# Charger_Board.net
KiCad netlist of a schematic drawn in EAGLE
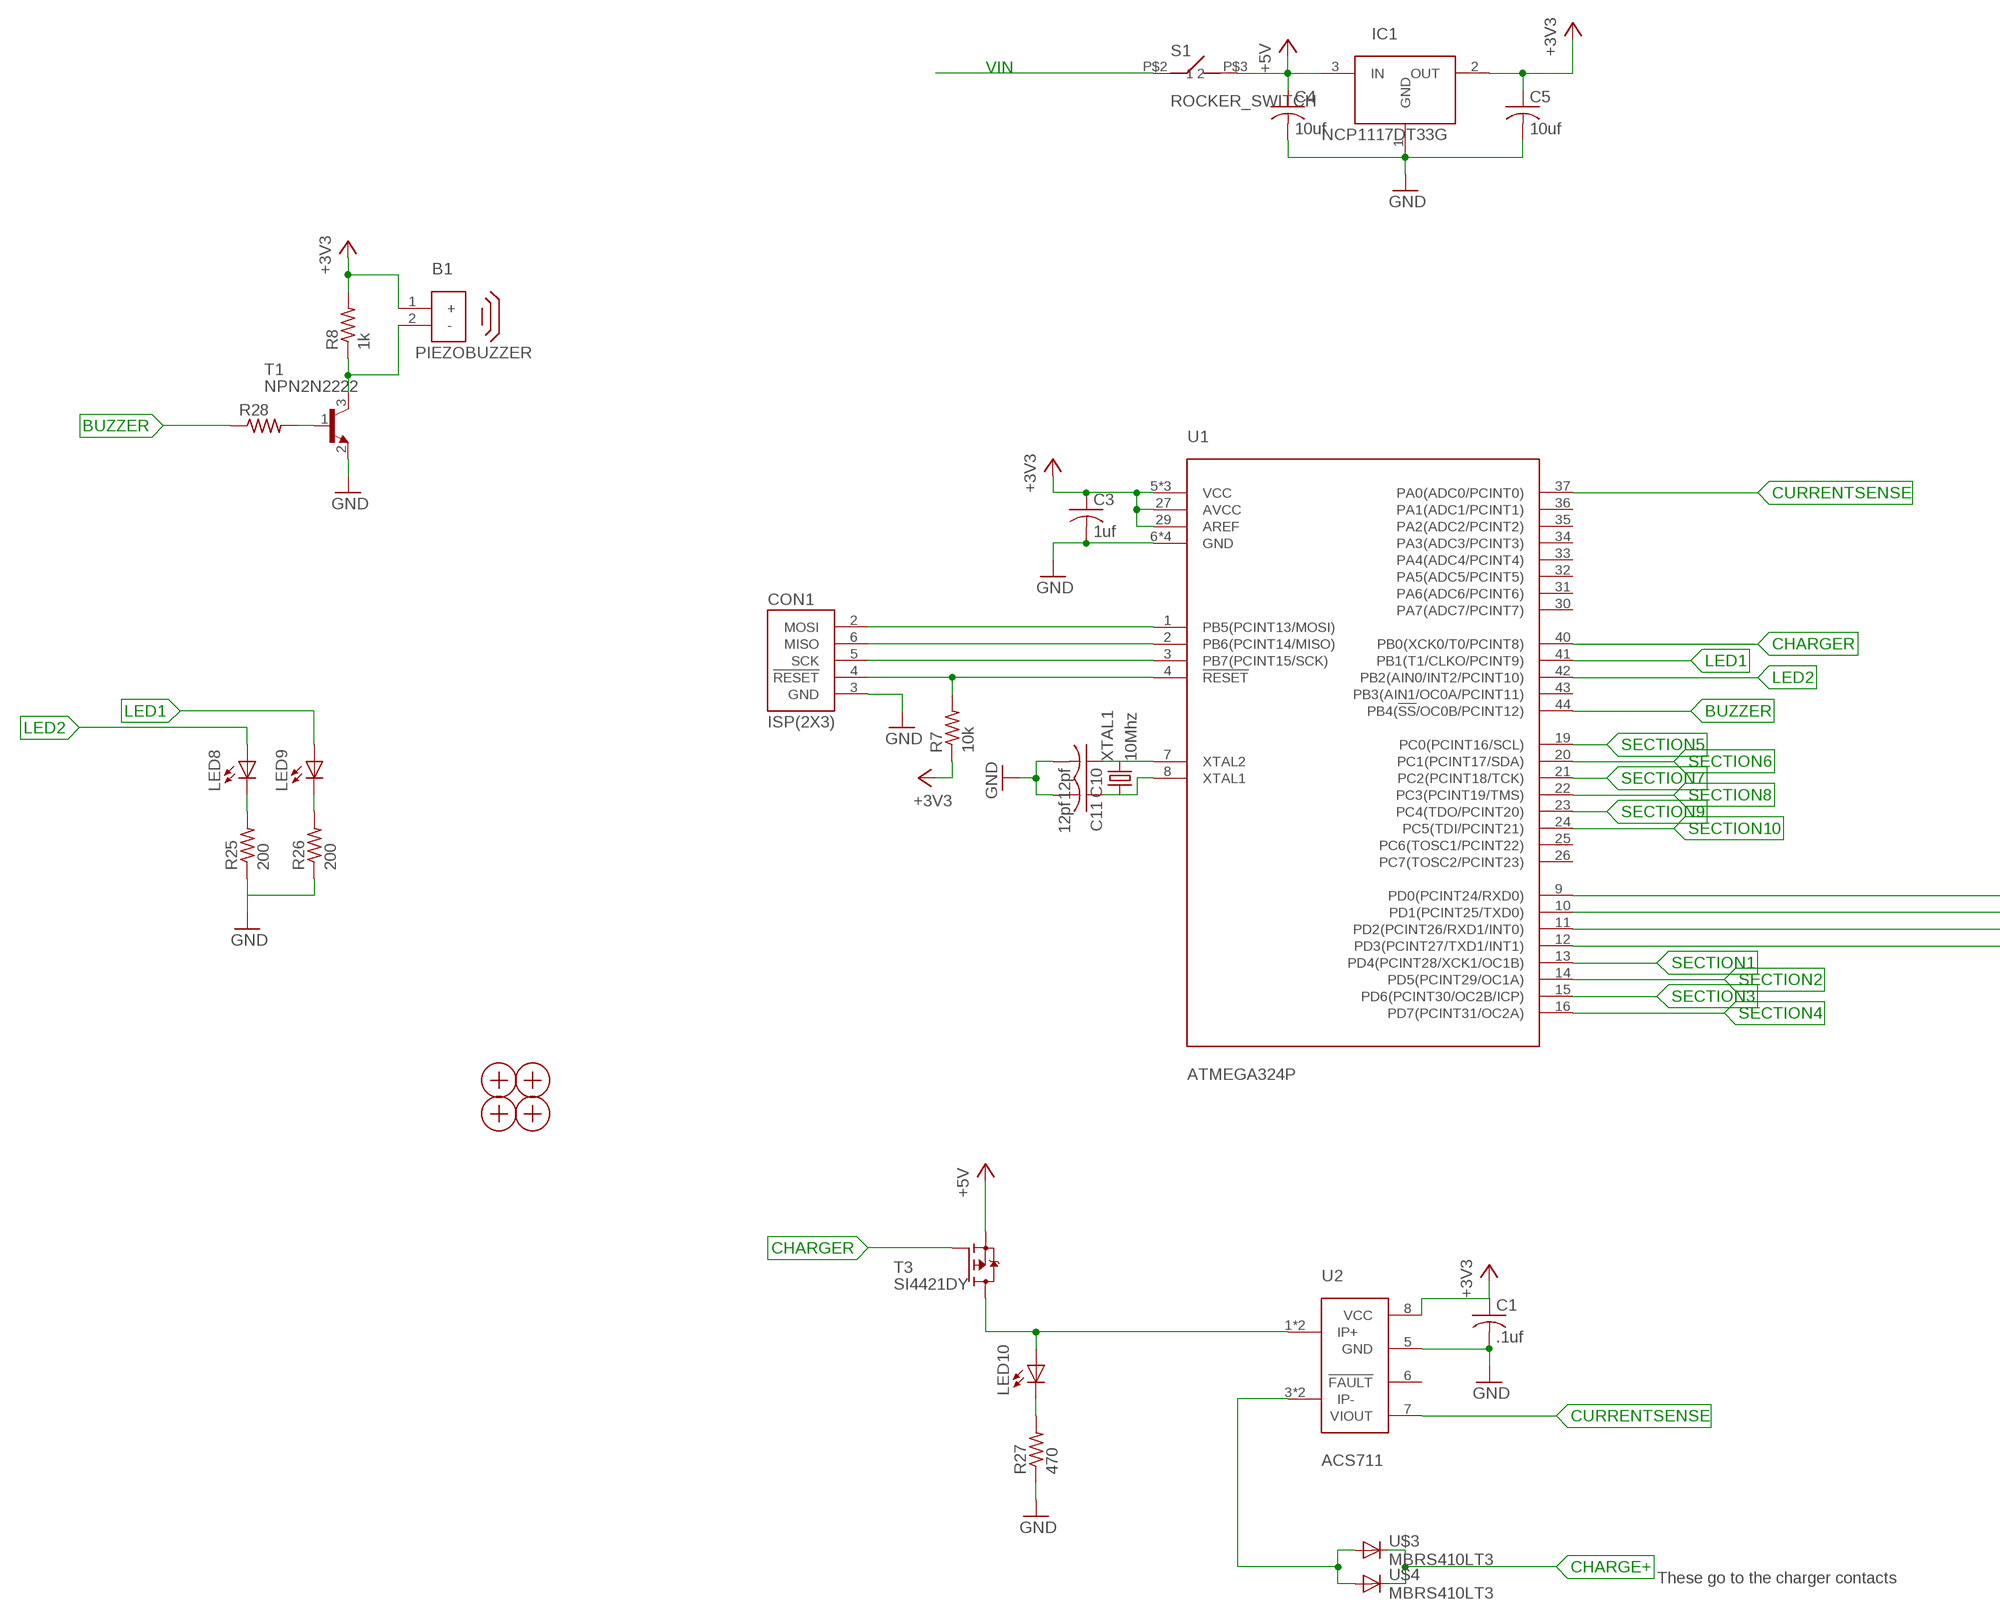
[diagram p0: schematic, sheet 1, part 1 of 2]
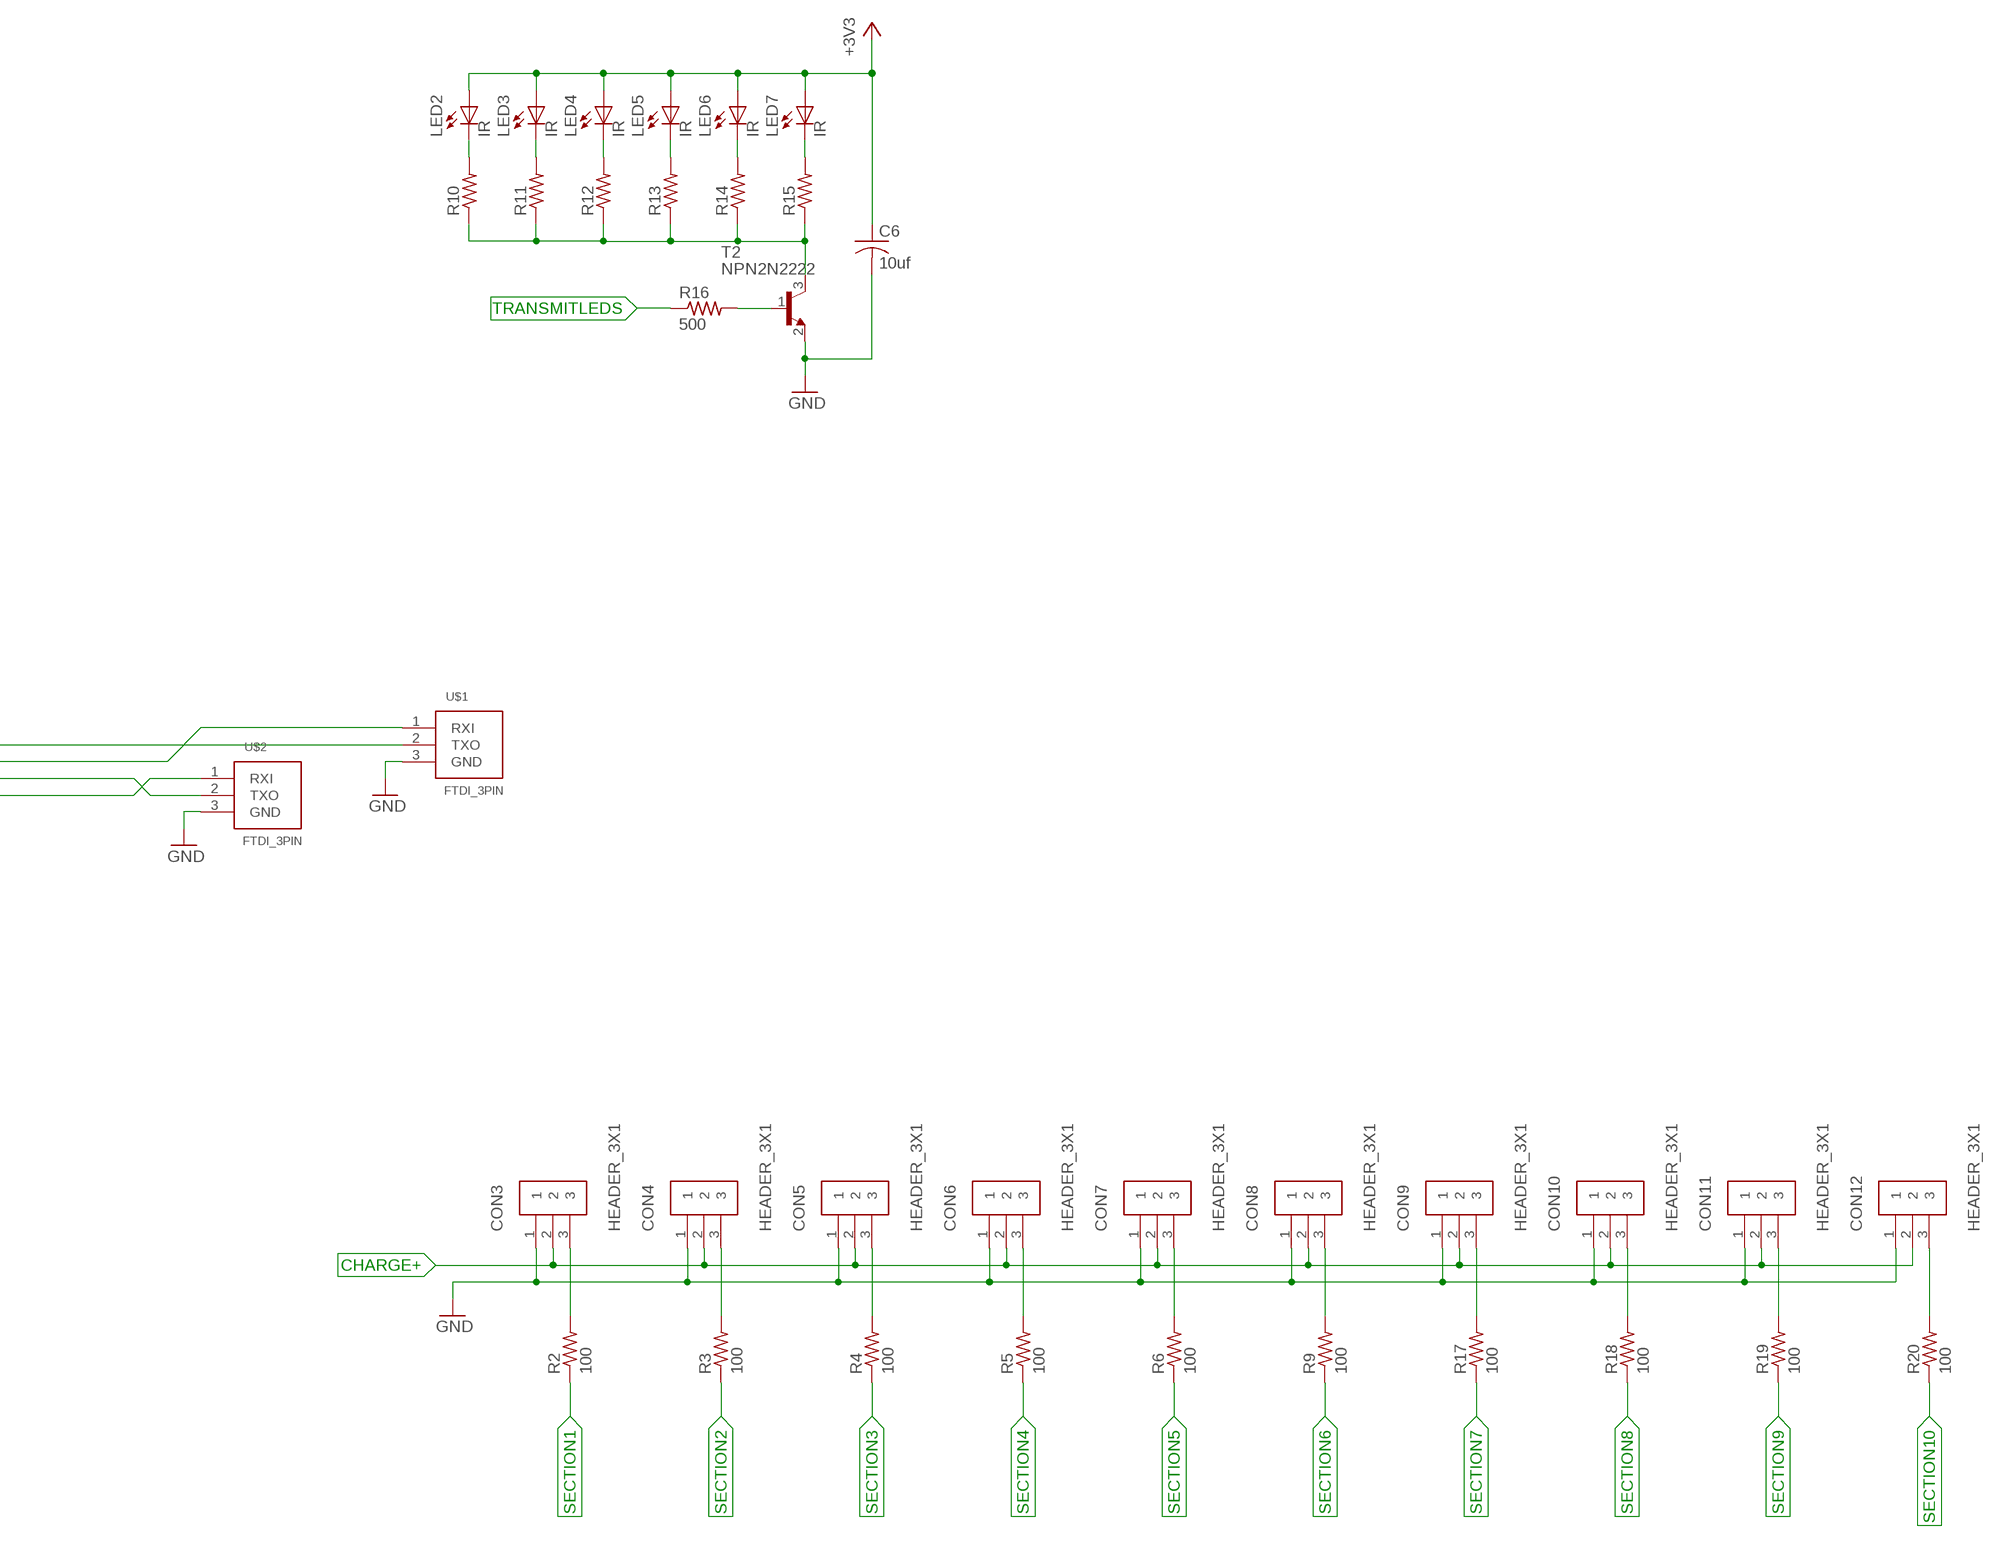
[diagram p1: schematic, sheet 1, part 2 of 2]

(export (version "E")
  (design (tool "Eeschema 10.0.6"))
  (components
    (comp (ref "B1")
      (value "PIEZOBUZZER")
      (footprint "eagle-import:PIEZOBUZZER")
      (libsource (lib "eagle-import") (part "PIEZOBUZZER"))
    )
    (comp (ref "C1")
      (value ".1uf")
      (footprint "eagle-import:0603")
      (libsource (lib "eagle-import") (part "CAP0603"))
    )
    (comp (ref "C3")
      (value "1uf")
      (footprint "eagle-import:0603")
      (libsource (lib "eagle-import") (part "CAP0603"))
    )
    (comp (ref "C4")
      (value "10uf")
      (footprint "eagle-import:0805")
      (libsource (lib "eagle-import") (part "CAP0805"))
    )
    (comp (ref "C5")
      (value "10uf")
      (footprint "eagle-import:0805")
      (libsource (lib "eagle-import") (part "CAP0805"))
    )
    (comp (ref "C6")
      (value "10uf")
      (footprint "eagle-import:0805")
      (libsource (lib "eagle-import") (part "CAP0805"))
    )
    (comp (ref "C10")
      (value "12pf")
      (footprint "eagle-import:0603")
      (libsource (lib "eagle-import") (part "CAP0603"))
    )
    (comp (ref "C11")
      (value "12pf")
      (footprint "eagle-import:0603")
      (libsource (lib "eagle-import") (part "CAP0603"))
    )
    (comp (ref "CON1")
      (value "ISP(2X3)")
      (footprint "eagle-import:PINHEADER(2X3)")
      (libsource (lib "eagle-import") (part "ISP(2X3)"))
    )
    (comp (ref "CON3")
      (value "HEADER_3X1")
      (footprint "eagle-import:3PINHEADER_.100_")
      (libsource (lib "eagle-import") (part "HEADER_3X1"))
    )
    (comp (ref "CON4")
      (value "HEADER_3X1")
      (footprint "eagle-import:3PINHEADER_.100_")
      (libsource (lib "eagle-import") (part "HEADER_3X1"))
    )
    (comp (ref "CON5")
      (value "HEADER_3X1")
      (footprint "eagle-import:3PINHEADER_.100_")
      (libsource (lib "eagle-import") (part "HEADER_3X1"))
    )
    (comp (ref "CON6")
      (value "HEADER_3X1")
      (footprint "eagle-import:3PINHEADER_.100_")
      (libsource (lib "eagle-import") (part "HEADER_3X1"))
    )
    (comp (ref "CON7")
      (value "HEADER_3X1")
      (footprint "eagle-import:3PINHEADER_.100_")
      (libsource (lib "eagle-import") (part "HEADER_3X1"))
    )
    (comp (ref "CON8")
      (value "HEADER_3X1")
      (footprint "eagle-import:3PINHEADER_.100_")
      (libsource (lib "eagle-import") (part "HEADER_3X1"))
    )
    (comp (ref "CON9")
      (value "HEADER_3X1")
      (footprint "eagle-import:3PINHEADER_.100_")
      (libsource (lib "eagle-import") (part "HEADER_3X1"))
    )
    (comp (ref "CON10")
      (value "HEADER_3X1")
      (footprint "eagle-import:3PINHEADER_.100_")
      (libsource (lib "eagle-import") (part "HEADER_3X1"))
    )
    (comp (ref "CON11")
      (value "HEADER_3X1")
      (footprint "eagle-import:3PINHEADER_.100_")
      (libsource (lib "eagle-import") (part "HEADER_3X1"))
    )
    (comp (ref "CON12")
      (value "HEADER_3X1")
      (footprint "eagle-import:3PINHEADER_.100_")
      (libsource (lib "eagle-import") (part "HEADER_3X1"))
    )
    (comp (ref "H1")
      (value "MOUNTINGHOLE")
      (footprint "eagle-import:MOUNTINGHOLE")
      (libsource (lib "eagle-import") (part "MOUNTINGHOLE"))
    )
    (comp (ref "H2")
      (value "MOUNTINGHOLE")
      (footprint "eagle-import:MOUNTINGHOLE")
      (libsource (lib "eagle-import") (part "MOUNTINGHOLE"))
    )
    (comp (ref "H3")
      (value "MOUNTINGHOLE")
      (footprint "eagle-import:MOUNTINGHOLE")
      (libsource (lib "eagle-import") (part "MOUNTINGHOLE"))
    )
    (comp (ref "H4")
      (value "MOUNTINGHOLE")
      (footprint "eagle-import:MOUNTINGHOLE")
      (libsource (lib "eagle-import") (part "MOUNTINGHOLE"))
    )
    (comp (ref "IC1")
      (value "NCP1117DT33G")
      (footprint "eagle-import:DPAK")
      (libsource (lib "eagle-import") (part "NCP1117DT33G"))
    )
    (comp (ref "LED2")
      (value "IR")
      (footprint "eagle-import:5MM_LED_RA")
      (libsource (lib "eagle-import") (part "LED5MMRA"))
    )
    (comp (ref "LED3")
      (value "IR")
      (footprint "eagle-import:5MM_LED_RA")
      (libsource (lib "eagle-import") (part "LED5MMRA"))
    )
    (comp (ref "LED4")
      (value "IR")
      (footprint "eagle-import:5MM_LED_RA")
      (libsource (lib "eagle-import") (part "LED5MMRA"))
    )
    (comp (ref "LED5")
      (value "IR")
      (footprint "eagle-import:5MM_LED_RA")
      (libsource (lib "eagle-import") (part "LED5MMRA"))
    )
    (comp (ref "LED6")
      (value "IR")
      (footprint "eagle-import:5MM_LED_RA")
      (libsource (lib "eagle-import") (part "LED5MMRA"))
    )
    (comp (ref "LED7")
      (value "IR")
      (footprint "eagle-import:5MM_LED_RA")
      (libsource (lib "eagle-import") (part "LED5MMRA"))
    )
    (comp (ref "LED8")
      (value "LED0603")
      (footprint "eagle-import:0603")
      (libsource (lib "eagle-import") (part "LED0603"))
    )
    (comp (ref "LED9")
      (value "LED0603")
      (footprint "eagle-import:0603")
      (libsource (lib "eagle-import") (part "LED0603"))
    )
    (comp (ref "LED10")
      (value "LED0603")
      (footprint "eagle-import:0603")
      (libsource (lib "eagle-import") (part "LED0603"))
    )
    (comp (ref "R2")
      (value "100")
      (footprint "eagle-import:0603")
      (libsource (lib "eagle-import") (part "RES0603"))
    )
    (comp (ref "R3")
      (value "100")
      (footprint "eagle-import:0603")
      (libsource (lib "eagle-import") (part "RES0603"))
    )
    (comp (ref "R4")
      (value "100")
      (footprint "eagle-import:0603")
      (libsource (lib "eagle-import") (part "RES0603"))
    )
    (comp (ref "R5")
      (value "100")
      (footprint "eagle-import:0603")
      (libsource (lib "eagle-import") (part "RES0603"))
    )
    (comp (ref "R6")
      (value "100")
      (footprint "eagle-import:0603")
      (libsource (lib "eagle-import") (part "RES0603"))
    )
    (comp (ref "R7")
      (value "10k")
      (footprint "eagle-import:0603")
      (libsource (lib "eagle-import") (part "RES0603"))
    )
    (comp (ref "R8")
      (value "1k")
      (footprint "eagle-import:0603")
      (libsource (lib "eagle-import") (part "RES0603"))
    )
    (comp (ref "R9")
      (value "100")
      (footprint "eagle-import:0603")
      (libsource (lib "eagle-import") (part "RES0603"))
    )
    (comp (ref "R10")
      (value "RES0603")
      (footprint "eagle-import:0603")
      (libsource (lib "eagle-import") (part "RES0603"))
    )
    (comp (ref "R11")
      (value "RES0603")
      (footprint "eagle-import:0603")
      (libsource (lib "eagle-import") (part "RES0603"))
    )
    (comp (ref "R12")
      (value "RES0603")
      (footprint "eagle-import:0603")
      (libsource (lib "eagle-import") (part "RES0603"))
    )
    (comp (ref "R13")
      (value "RES0603")
      (footprint "eagle-import:0603")
      (libsource (lib "eagle-import") (part "RES0603"))
    )
    (comp (ref "R14")
      (value "RES0603")
      (footprint "eagle-import:0603")
      (libsource (lib "eagle-import") (part "RES0603"))
    )
    (comp (ref "R15")
      (value "RES0603")
      (footprint "eagle-import:0603")
      (libsource (lib "eagle-import") (part "RES0603"))
    )
    (comp (ref "R16")
      (value "500")
      (footprint "eagle-import:0603")
      (libsource (lib "eagle-import") (part "RES0603"))
    )
    (comp (ref "R17")
      (value "100")
      (footprint "eagle-import:0603")
      (libsource (lib "eagle-import") (part "RES0603"))
    )
    (comp (ref "R18")
      (value "100")
      (footprint "eagle-import:0603")
      (libsource (lib "eagle-import") (part "RES0603"))
    )
    (comp (ref "R19")
      (value "100")
      (footprint "eagle-import:0603")
      (libsource (lib "eagle-import") (part "RES0603"))
    )
    (comp (ref "R20")
      (value "100")
      (footprint "eagle-import:0603")
      (libsource (lib "eagle-import") (part "RES0603"))
    )
    (comp (ref "R25")
      (value "200")
      (footprint "eagle-import:0603")
      (libsource (lib "eagle-import") (part "RES0603"))
    )
    (comp (ref "R26")
      (value "200")
      (footprint "eagle-import:0603")
      (libsource (lib "eagle-import") (part "RES0603"))
    )
    (comp (ref "R27")
      (value "470")
      (footprint "eagle-import:0603")
      (libsource (lib "eagle-import") (part "RES0603"))
    )
    (comp (ref "R28")
      (value "RES0603")
      (footprint "eagle-import:0603")
      (libsource (lib "eagle-import") (part "RES0603"))
    )
    (comp (ref "S1")
      (value "ROCKER_SWITCH")
      (footprint "eagle-import:DUMMY")
      (libsource (lib "eagle-import") (part "ROCKER_SWITCH"))
    )
    (comp (ref "T1")
      (value "NPN2N2222")
      (footprint "eagle-import:SOT23")
      (libsource (lib "eagle-import") (part "NPN2N2222"))
    )
    (comp (ref "T2")
      (value "NPN2N2222")
      (footprint "eagle-import:SOT23")
      (libsource (lib "eagle-import") (part "NPN2N2222"))
    )
    (comp (ref "T3")
      (value "SI4421DY")
      (footprint "eagle-import:S0-8")
      (libsource (lib "eagle-import") (part "SI4421DY"))
    )
    (comp (ref "U$1")
      (value "FTDI_3PIN")
      (footprint "eagle-import:3PINHEADER_.100_")
      (libsource (lib "eagle-import") (part "FTDI_3PIN"))
    )
    (comp (ref "U$2")
      (value "FTDI_3PIN")
      (footprint "eagle-import:3PINHEADER_.100_")
      (libsource (lib "eagle-import") (part "FTDI_3PIN"))
    )
    (comp (ref "U$3")
      (value "MBRS410LT3")
      (footprint "eagle-import:SMD_DIODE")
      (libsource (lib "eagle-import") (part "MBRS410LT3"))
    )
    (comp (ref "U$4")
      (value "MBRS410LT3")
      (footprint "eagle-import:SMD_DIODE")
      (libsource (lib "eagle-import") (part "MBRS410LT3"))
    )
    (comp (ref "U1")
      (value "ATMEGA324P")
      (footprint "eagle-import:TQFP44")
      (libsource (lib "eagle-import") (part "ATMEGA324P"))
    )
    (comp (ref "U2")
      (value "ACS711")
      (footprint "eagle-import:8SOIC")
      (libsource (lib "eagle-import") (part "ACS711"))
    )
    (comp (ref "XTAL1")
      (value "10Mhz")
      (footprint "eagle-import:SMDXTAL")
      (libsource (lib "eagle-import") (part "NX5032GA-10.000000MHZ"))
    )
  )
  (nets
    (net (code "1") (name "+3V3") (class "Default")
      (node (ref "B1") (pin "1") (pinfunction "+_1") (pintype "bidirectional"))
      (node (ref "C1") (pin "1") (pinfunction "1_1") (pintype "passive"))
      (node (ref "C3") (pin "1") (pinfunction "1_1") (pintype "passive"))
      (node (ref "C5") (pin "1") (pinfunction "1_1") (pintype "passive"))
      (node (ref "C6") (pin "1") (pinfunction "1_1") (pintype "passive"))
      (node (ref "IC1") (pin "2") (pinfunction "OUT_2") (pintype "bidirectional"))
      (node (ref "LED2") (pin "1") (pinfunction "A_1") (pintype "passive"))
      (node (ref "LED3") (pin "1") (pinfunction "A_1") (pintype "passive"))
      (node (ref "LED4") (pin "1") (pinfunction "A_1") (pintype "passive"))
      (node (ref "LED5") (pin "1") (pinfunction "A_1") (pintype "passive"))
      (node (ref "LED6") (pin "1") (pinfunction "A_1") (pintype "passive"))
      (node (ref "LED7") (pin "1") (pinfunction "A_1") (pintype "passive"))
      (node (ref "R7") (pin "1") (pinfunction "1_1") (pintype "passive"))
      (node (ref "R8") (pin "2") (pinfunction "2_2") (pintype "passive"))
      (node (ref "U1") (pin "17") (pinfunction "VCC_17") (pintype "bidirectional"))
      (node (ref "U1") (pin "27") (pinfunction "AVCC_27") (pintype "bidirectional"))
      (node (ref "U1") (pin "29") (pinfunction "AREF_29") (pintype "bidirectional"))
      (node (ref "U1") (pin "38") (pinfunction "VCC_38") (pintype "bidirectional"))
      (node (ref "U1") (pin "5") (pinfunction "VCC_5") (pintype "bidirectional"))
      (node (ref "U2") (pin "8") (pinfunction "VCC_8") (pintype "bidirectional"))
    )
    (net (code "2") (name "+5V") (class "Default")
      (node (ref "C4") (pin "1") (pinfunction "1_1") (pintype "passive"))
      (node (ref "IC1") (pin "3") (pinfunction "IN_3") (pintype "bidirectional"))
      (node (ref "S1") (pin "P$3") (pinfunction "2_P$3") (pintype "bidirectional"))
      (node (ref "T3") (pin "1") (pinfunction "S_1") (pintype "passive"))
      (node (ref "T3") (pin "2") (pinfunction "S_2") (pintype "passive"))
      (node (ref "T3") (pin "3") (pinfunction "S_3") (pintype "passive"))
    )
    (net (code "3") (name "/VIN") (class "Default")
      (node (ref "S1") (pin "P$2") (pinfunction "1_P$2") (pintype "bidirectional"))
    )
    (net (code "4") (name "BUZZER") (class "Default")
      (node (ref "R28") (pin "1") (pinfunction "1_1") (pintype "passive"))
      (node (ref "U1") (pin "44") (pinfunction "PB4(~{SS}/OC0B/PCINT12)_44") (pintype "bidirectional"))
    )
    (net (code "5") (name "CHARGE+") (class "Default")
      (node (ref "CON10") (pin "2") (pinfunction "2_2") (pintype "bidirectional"))
      (node (ref "CON11") (pin "2") (pinfunction "2_2") (pintype "bidirectional"))
      (node (ref "CON12") (pin "2") (pinfunction "2_2") (pintype "bidirectional"))
      (node (ref "CON3") (pin "2") (pinfunction "2_2") (pintype "bidirectional"))
      (node (ref "CON4") (pin "2") (pinfunction "2_2") (pintype "bidirectional"))
      (node (ref "CON5") (pin "2") (pinfunction "2_2") (pintype "bidirectional"))
      (node (ref "CON6") (pin "2") (pinfunction "2_2") (pintype "bidirectional"))
      (node (ref "CON7") (pin "2") (pinfunction "2_2") (pintype "bidirectional"))
      (node (ref "CON8") (pin "2") (pinfunction "2_2") (pintype "bidirectional"))
      (node (ref "CON9") (pin "2") (pinfunction "2_2") (pintype "bidirectional"))
      (node (ref "U$3") (pin "2") (pinfunction "C_2") (pintype "passive"))
      (node (ref "U$4") (pin "2") (pinfunction "C_2") (pintype "passive"))
    )
    (net (code "6") (name "CHARGER") (class "Default")
      (node (ref "T3") (pin "4") (pinfunction "G_4") (pintype "passive"))
      (node (ref "U1") (pin "40") (pinfunction "PB0(XCK0/T0/PCINT8)_40") (pintype "bidirectional"))
    )
    (net (code "7") (name "CURRENTSENSE") (class "Default")
      (node (ref "U1") (pin "37") (pinfunction "PA0(ADC0/PCINT0)_37") (pintype "bidirectional"))
      (node (ref "U2") (pin "7") (pinfunction "VIOUT_7") (pintype "bidirectional"))
    )
    (net (code "8") (name "GND") (class "Default")
      (node (ref "C1") (pin "2") (pinfunction "2_2") (pintype "passive"))
      (node (ref "C10") (pin "2") (pinfunction "2_2") (pintype "passive"))
      (node (ref "C11") (pin "2") (pinfunction "2_2") (pintype "passive"))
      (node (ref "C3") (pin "2") (pinfunction "2_2") (pintype "passive"))
      (node (ref "C4") (pin "2") (pinfunction "2_2") (pintype "passive"))
      (node (ref "C5") (pin "2") (pinfunction "2_2") (pintype "passive"))
      (node (ref "C6") (pin "2") (pinfunction "2_2") (pintype "passive"))
      (node (ref "CON1") (pin "3") (pinfunction "GND_3") (pintype "bidirectional"))
      (node (ref "CON10") (pin "1") (pinfunction "1_1") (pintype "bidirectional"))
      (node (ref "CON11") (pin "1") (pinfunction "1_1") (pintype "bidirectional"))
      (node (ref "CON12") (pin "1") (pinfunction "1_1") (pintype "bidirectional"))
      (node (ref "CON3") (pin "1") (pinfunction "1_1") (pintype "bidirectional"))
      (node (ref "CON4") (pin "1") (pinfunction "1_1") (pintype "bidirectional"))
      (node (ref "CON5") (pin "1") (pinfunction "1_1") (pintype "bidirectional"))
      (node (ref "CON6") (pin "1") (pinfunction "1_1") (pintype "bidirectional"))
      (node (ref "CON7") (pin "1") (pinfunction "1_1") (pintype "bidirectional"))
      (node (ref "CON8") (pin "1") (pinfunction "1_1") (pintype "bidirectional"))
      (node (ref "CON9") (pin "1") (pinfunction "1_1") (pintype "bidirectional"))
      (node (ref "IC1") (pin "1") (pinfunction "GND_1") (pintype "bidirectional"))
      (node (ref "R25") (pin "1") (pinfunction "1_1") (pintype "passive"))
      (node (ref "R26") (pin "1") (pinfunction "1_1") (pintype "passive"))
      (node (ref "R27") (pin "1") (pinfunction "1_1") (pintype "passive"))
      (node (ref "T1") (pin "2") (pinfunction "E_2") (pintype "passive"))
      (node (ref "T2") (pin "2") (pinfunction "E_2") (pintype "passive"))
      (node (ref "U$1") (pin "3") (pinfunction "GND_3") (pintype "bidirectional"))
      (node (ref "U$2") (pin "3") (pinfunction "GND_3") (pintype "bidirectional"))
      (node (ref "U1") (pin "18") (pinfunction "GND_18") (pintype "bidirectional"))
      (node (ref "U1") (pin "28") (pinfunction "GND_28") (pintype "bidirectional"))
      (node (ref "U1") (pin "39") (pinfunction "GND_39") (pintype "bidirectional"))
      (node (ref "U1") (pin "6") (pinfunction "GND_6") (pintype "bidirectional"))
      (node (ref "U2") (pin "5") (pinfunction "GND_5") (pintype "bidirectional"))
    )
    (net (code "9") (name "LED1") (class "Default")
      (node (ref "LED9") (pin "2") (pinfunction "A_2") (pintype "passive"))
      (node (ref "U1") (pin "41") (pinfunction "PB1(T1/CLKO/PCINT9)_41") (pintype "bidirectional"))
    )
    (net (code "10") (name "LED2") (class "Default")
      (node (ref "LED8") (pin "2") (pinfunction "A_2") (pintype "passive"))
      (node (ref "U1") (pin "42") (pinfunction "PB2(AIN0/INT2/PCINT10)_42") (pintype "bidirectional"))
    )
    (net (code "11") (name "Net-(B1--)") (class "Default")
      (node (ref "B1") (pin "2") (pinfunction "-_2") (pintype "bidirectional"))
      (node (ref "R8") (pin "1") (pinfunction "1_1") (pintype "passive"))
      (node (ref "T1") (pin "3") (pinfunction "C_3") (pintype "passive"))
    )
    (net (code "12") (name "Net-(CON1-MISO)") (class "Default")
      (node (ref "CON1") (pin "6") (pinfunction "MISO_6") (pintype "bidirectional"))
      (node (ref "U1") (pin "2") (pinfunction "PB6(PCINT14/MISO)_2") (pintype "bidirectional"))
    )
    (net (code "13") (name "Net-(CON1-MOSI)") (class "Default")
      (node (ref "CON1") (pin "2") (pinfunction "MOSI_2") (pintype "bidirectional"))
      (node (ref "U1") (pin "1") (pinfunction "PB5(PCINT13/MOSI)_1") (pintype "bidirectional"))
    )
    (net (code "14") (name "Net-(CON1-SCK)") (class "Default")
      (node (ref "CON1") (pin "5") (pinfunction "SCK_5") (pintype "bidirectional"))
      (node (ref "U1") (pin "3") (pinfunction "PB7(PCINT15/SCK)_3") (pintype "bidirectional"))
    )
    (net (code "15") (name "Net-(CON1-~{RESET})") (class "Default")
      (node (ref "CON1") (pin "4") (pinfunction "~{RESET}_4") (pintype "bidirectional"))
      (node (ref "R7") (pin "2") (pinfunction "2_2") (pintype "passive"))
      (node (ref "U1") (pin "4") (pinfunction "~{RESET}_4") (pintype "bidirectional"))
    )
    (net (code "16") (name "Net-(CON3-Pad3)") (class "Default")
      (node (ref "CON3") (pin "3") (pinfunction "3_3") (pintype "bidirectional"))
      (node (ref "R2") (pin "2") (pinfunction "2_2") (pintype "passive"))
    )
    (net (code "17") (name "Net-(CON4-Pad3)") (class "Default")
      (node (ref "CON4") (pin "3") (pinfunction "3_3") (pintype "bidirectional"))
      (node (ref "R3") (pin "2") (pinfunction "2_2") (pintype "passive"))
    )
    (net (code "18") (name "Net-(CON5-Pad3)") (class "Default")
      (node (ref "CON5") (pin "3") (pinfunction "3_3") (pintype "bidirectional"))
      (node (ref "R4") (pin "2") (pinfunction "2_2") (pintype "passive"))
    )
    (net (code "19") (name "Net-(CON6-Pad3)") (class "Default")
      (node (ref "CON6") (pin "3") (pinfunction "3_3") (pintype "bidirectional"))
      (node (ref "R5") (pin "2") (pinfunction "2_2") (pintype "passive"))
    )
    (net (code "20") (name "Net-(CON7-Pad3)") (class "Default")
      (node (ref "CON7") (pin "3") (pinfunction "3_3") (pintype "bidirectional"))
      (node (ref "R6") (pin "2") (pinfunction "2_2") (pintype "passive"))
    )
    (net (code "21") (name "Net-(CON8-Pad3)") (class "Default")
      (node (ref "CON8") (pin "3") (pinfunction "3_3") (pintype "bidirectional"))
      (node (ref "R9") (pin "2") (pinfunction "2_2") (pintype "passive"))
    )
    (net (code "22") (name "Net-(CON9-Pad3)") (class "Default")
      (node (ref "CON9") (pin "3") (pinfunction "3_3") (pintype "bidirectional"))
      (node (ref "R17") (pin "2") (pinfunction "2_2") (pintype "passive"))
    )
    (net (code "23") (name "Net-(CON10-Pad3)") (class "Default")
      (node (ref "CON10") (pin "3") (pinfunction "3_3") (pintype "bidirectional"))
      (node (ref "R18") (pin "2") (pinfunction "2_2") (pintype "passive"))
    )
    (net (code "24") (name "Net-(CON11-Pad3)") (class "Default")
      (node (ref "CON11") (pin "3") (pinfunction "3_3") (pintype "bidirectional"))
      (node (ref "R19") (pin "2") (pinfunction "2_2") (pintype "passive"))
    )
    (net (code "25") (name "Net-(CON12-Pad3)") (class "Default")
      (node (ref "CON12") (pin "3") (pinfunction "3_3") (pintype "bidirectional"))
      (node (ref "R20") (pin "2") (pinfunction "2_2") (pintype "passive"))
    )
    (net (code "26") (name "Net-(LED2-C)") (class "Default")
      (node (ref "LED2") (pin "2") (pinfunction "C_2") (pintype "passive"))
      (node (ref "R10") (pin "2") (pinfunction "2_2") (pintype "passive"))
    )
    (net (code "27") (name "Net-(LED3-C)") (class "Default")
      (node (ref "LED3") (pin "2") (pinfunction "C_2") (pintype "passive"))
      (node (ref "R11") (pin "2") (pinfunction "2_2") (pintype "passive"))
    )
    (net (code "28") (name "Net-(LED4-C)") (class "Default")
      (node (ref "LED4") (pin "2") (pinfunction "C_2") (pintype "passive"))
      (node (ref "R12") (pin "2") (pinfunction "2_2") (pintype "passive"))
    )
    (net (code "29") (name "Net-(LED5-C)") (class "Default")
      (node (ref "LED5") (pin "2") (pinfunction "C_2") (pintype "passive"))
      (node (ref "R13") (pin "2") (pinfunction "2_2") (pintype "passive"))
    )
    (net (code "30") (name "Net-(LED6-C)") (class "Default")
      (node (ref "LED6") (pin "2") (pinfunction "C_2") (pintype "passive"))
      (node (ref "R14") (pin "2") (pinfunction "2_2") (pintype "passive"))
    )
    (net (code "31") (name "Net-(LED7-C)") (class "Default")
      (node (ref "LED7") (pin "2") (pinfunction "C_2") (pintype "passive"))
      (node (ref "R15") (pin "2") (pinfunction "2_2") (pintype "passive"))
    )
    (net (code "32") (name "Net-(LED8-C)") (class "Default")
      (node (ref "LED8") (pin "1") (pinfunction "C_1") (pintype "passive"))
      (node (ref "R25") (pin "2") (pinfunction "2_2") (pintype "passive"))
    )
    (net (code "33") (name "Net-(LED9-C)") (class "Default")
      (node (ref "LED9") (pin "1") (pinfunction "C_1") (pintype "passive"))
      (node (ref "R26") (pin "2") (pinfunction "2_2") (pintype "passive"))
    )
    (net (code "34") (name "Net-(LED10-A)") (class "Default")
      (node (ref "LED10") (pin "2") (pinfunction "A_2") (pintype "passive"))
      (node (ref "T3") (pin "5") (pinfunction "D_5") (pintype "passive"))
      (node (ref "T3") (pin "6") (pinfunction "D_6") (pintype "passive"))
      (node (ref "T3") (pin "7") (pinfunction "D_7") (pintype "passive"))
      (node (ref "T3") (pin "8") (pinfunction "D_8") (pintype "passive"))
      (node (ref "U2") (pin "1") (pinfunction "IP+_1") (pintype "bidirectional"))
      (node (ref "U2") (pin "2") (pinfunction "IP+_2") (pintype "bidirectional"))
    )
    (net (code "35") (name "Net-(LED10-C)") (class "Default")
      (node (ref "LED10") (pin "1") (pinfunction "C_1") (pintype "passive"))
      (node (ref "R27") (pin "2") (pinfunction "2_2") (pintype "passive"))
    )
    (net (code "36") (name "Net-(T1-B)") (class "Default")
      (node (ref "R28") (pin "2") (pinfunction "2_2") (pintype "passive"))
      (node (ref "T1") (pin "1") (pinfunction "B_1") (pintype "passive"))
    )
    (net (code "37") (name "Net-(T2-B)") (class "Default")
      (node (ref "R16") (pin "2") (pinfunction "2_2") (pintype "passive"))
      (node (ref "T2") (pin "1") (pinfunction "B_1") (pintype "passive"))
    )
    (net (code "38") (name "Net-(T2-C)") (class "Default")
      (node (ref "R10") (pin "1") (pinfunction "1_1") (pintype "passive"))
      (node (ref "R11") (pin "1") (pinfunction "1_1") (pintype "passive"))
      (node (ref "R12") (pin "1") (pinfunction "1_1") (pintype "passive"))
      (node (ref "R13") (pin "1") (pinfunction "1_1") (pintype "passive"))
      (node (ref "R14") (pin "1") (pinfunction "1_1") (pintype "passive"))
      (node (ref "R15") (pin "1") (pinfunction "1_1") (pintype "passive"))
      (node (ref "T2") (pin "3") (pinfunction "C_3") (pintype "passive"))
    )
    (net (code "39") (name "Net-(U$1-RXI)") (class "Default")
      (node (ref "U$1") (pin "1") (pinfunction "RXI_1") (pintype "bidirectional"))
      (node (ref "U1") (pin "10") (pinfunction "PD1(PCINT25/TXD0)_10") (pintype "bidirectional"))
    )
    (net (code "40") (name "Net-(U$1-TXO)") (class "Default")
      (node (ref "U$1") (pin "2") (pinfunction "TXO_2") (pintype "bidirectional"))
      (node (ref "U1") (pin "9") (pinfunction "PD0(PCINT24/RXD0)_9") (pintype "bidirectional"))
    )
    (net (code "41") (name "Net-(U$2-RXI)") (class "Default")
      (node (ref "U$2") (pin "1") (pinfunction "RXI_1") (pintype "bidirectional"))
      (node (ref "U1") (pin "12") (pinfunction "PD3(PCINT27/TXD1/INT1)_12") (pintype "bidirectional"))
    )
    (net (code "42") (name "Net-(U$2-TXO)") (class "Default")
      (node (ref "U$2") (pin "2") (pinfunction "TXO_2") (pintype "bidirectional"))
      (node (ref "U1") (pin "11") (pinfunction "PD2(PCINT26/RXD1/INT0)_11") (pintype "bidirectional"))
    )
    (net (code "43") (name "Net-(U$3-A)") (class "Default")
      (node (ref "U$3") (pin "1") (pinfunction "A_1") (pintype "passive"))
      (node (ref "U$4") (pin "1") (pinfunction "A_1") (pintype "passive"))
      (node (ref "U2") (pin "3") (pinfunction "IP-_3") (pintype "bidirectional"))
      (node (ref "U2") (pin "4") (pinfunction "IP-_4") (pintype "bidirectional"))
    )
    (net (code "44") (name "Net-(U1-XTAL1)") (class "Default")
      (node (ref "C11") (pin "1") (pinfunction "1_1") (pintype "passive"))
      (node (ref "U1") (pin "8") (pinfunction "XTAL1_8") (pintype "bidirectional"))
      (node (ref "XTAL1") (pin "1") (pinfunction "1_1") (pintype "passive"))
    )
    (net (code "45") (name "Net-(U1-XTAL2)") (class "Default")
      (node (ref "C10") (pin "1") (pinfunction "1_1") (pintype "passive"))
      (node (ref "U1") (pin "7") (pinfunction "XTAL2_7") (pintype "bidirectional"))
      (node (ref "XTAL1") (pin "2") (pinfunction "2_2") (pintype "passive"))
    )
    (net (code "46") (name "SECTION1") (class "Default")
      (node (ref "R2") (pin "1") (pinfunction "1_1") (pintype "passive"))
      (node (ref "U1") (pin "13") (pinfunction "PD4(PCINT28/XCK1/OC1B)_13") (pintype "bidirectional"))
    )
    (net (code "47") (name "SECTION2") (class "Default")
      (node (ref "R3") (pin "1") (pinfunction "1_1") (pintype "passive"))
      (node (ref "U1") (pin "14") (pinfunction "PD5(PCINT29/OC1A)_14") (pintype "bidirectional"))
    )
    (net (code "48") (name "SECTION3") (class "Default")
      (node (ref "R4") (pin "1") (pinfunction "1_1") (pintype "passive"))
      (node (ref "U1") (pin "15") (pinfunction "PD6(PCINT30/OC2B/ICP)_15") (pintype "bidirectional"))
    )
    (net (code "49") (name "SECTION4") (class "Default")
      (node (ref "R5") (pin "1") (pinfunction "1_1") (pintype "passive"))
      (node (ref "U1") (pin "16") (pinfunction "PD7(PCINT31/OC2A)_16") (pintype "bidirectional"))
    )
    (net (code "50") (name "SECTION5") (class "Default")
      (node (ref "R6") (pin "1") (pinfunction "1_1") (pintype "passive"))
      (node (ref "U1") (pin "19") (pinfunction "PC0(PCINT16/SCL)_19") (pintype "bidirectional"))
    )
    (net (code "51") (name "SECTION6") (class "Default")
      (node (ref "R9") (pin "1") (pinfunction "1_1") (pintype "passive"))
      (node (ref "U1") (pin "20") (pinfunction "PC1(PCINT17/SDA)_20") (pintype "bidirectional"))
    )
    (net (code "52") (name "SECTION7") (class "Default")
      (node (ref "R17") (pin "1") (pinfunction "1_1") (pintype "passive"))
      (node (ref "U1") (pin "21") (pinfunction "PC2(PCINT18/TCK)_21") (pintype "bidirectional"))
    )
    (net (code "53") (name "SECTION8") (class "Default")
      (node (ref "R18") (pin "1") (pinfunction "1_1") (pintype "passive"))
      (node (ref "U1") (pin "22") (pinfunction "PC3(PCINT19/TMS)_22") (pintype "bidirectional"))
    )
    (net (code "54") (name "SECTION9") (class "Default")
      (node (ref "R19") (pin "1") (pinfunction "1_1") (pintype "passive"))
      (node (ref "U1") (pin "23") (pinfunction "PC4(TDO/PCINT20)_23") (pintype "bidirectional"))
    )
    (net (code "55") (name "SECTION10") (class "Default")
      (node (ref "R20") (pin "1") (pinfunction "1_1") (pintype "passive"))
      (node (ref "U1") (pin "24") (pinfunction "PC5(TDI/PCINT21)_24") (pintype "bidirectional"))
    )
    (net (code "56") (name "TRANSMITLEDS") (class "Default")
      (node (ref "R16") (pin "1") (pinfunction "1_1") (pintype "passive"))
    )
    (net (code "57") (name "unconnected-(U1-PA1(ADC1{slash}PCINT1)-Pad36)") (class "Default")
      (node (ref "U1") (pin "36") (pinfunction "PA1(ADC1/PCINT1)_36") (pintype "bidirectional"))
    )
    (net (code "58") (name "unconnected-(U1-PA2(ADC2{slash}PCINT2)-Pad35)") (class "Default")
      (node (ref "U1") (pin "35") (pinfunction "PA2(ADC2/PCINT2)_35") (pintype "bidirectional"))
    )
    (net (code "59") (name "unconnected-(U1-PA3(ADC3{slash}PCINT3)-Pad34)") (class "Default")
      (node (ref "U1") (pin "34") (pinfunction "PA3(ADC3/PCINT3)_34") (pintype "bidirectional"))
    )
    (net (code "60") (name "unconnected-(U1-PA4(ADC4{slash}PCINT4)-Pad33)") (class "Default")
      (node (ref "U1") (pin "33") (pinfunction "PA4(ADC4/PCINT4)_33") (pintype "bidirectional"))
    )
    (net (code "61") (name "unconnected-(U1-PA5(ADC5{slash}PCINT5)-Pad32)") (class "Default")
      (node (ref "U1") (pin "32") (pinfunction "PA5(ADC5/PCINT5)_32") (pintype "bidirectional"))
    )
    (net (code "62") (name "unconnected-(U1-PA6(ADC6{slash}PCINT6)-Pad31)") (class "Default")
      (node (ref "U1") (pin "31") (pinfunction "PA6(ADC6/PCINT6)_31") (pintype "bidirectional"))
    )
    (net (code "63") (name "unconnected-(U1-PA7(ADC7{slash}PCINT7)-Pad30)") (class "Default")
      (node (ref "U1") (pin "30") (pinfunction "PA7(ADC7/PCINT7)_30") (pintype "bidirectional"))
    )
    (net (code "64") (name "unconnected-(U1-PB3(AIN1{slash}OC0A{slash}PCINT11)-Pad43)") (class "Default")
      (node (ref "U1") (pin "43") (pinfunction "PB3(AIN1/OC0A/PCINT11)_43") (pintype "bidirectional"))
    )
    (net (code "65") (name "unconnected-(U1-PC6(TOSC1{slash}PCINT22)-Pad25)") (class "Default")
      (node (ref "U1") (pin "25") (pinfunction "PC6(TOSC1/PCINT22)_25") (pintype "bidirectional"))
    )
    (net (code "66") (name "unconnected-(U1-PC7(TOSC2{slash}PCINT23)-Pad26)") (class "Default")
      (node (ref "U1") (pin "26") (pinfunction "PC7(TOSC2/PCINT23)_26") (pintype "bidirectional"))
    )
    (net (code "67") (name "unconnected-(U2-~{FAULT}-Pad6)") (class "Default")
      (node (ref "U2") (pin "6") (pinfunction "~{FAULT}_6") (pintype "bidirectional"))
    )
  )
)
